# Power_Supply.net
KiCad netlist of a schematic drawn in Altium Designer
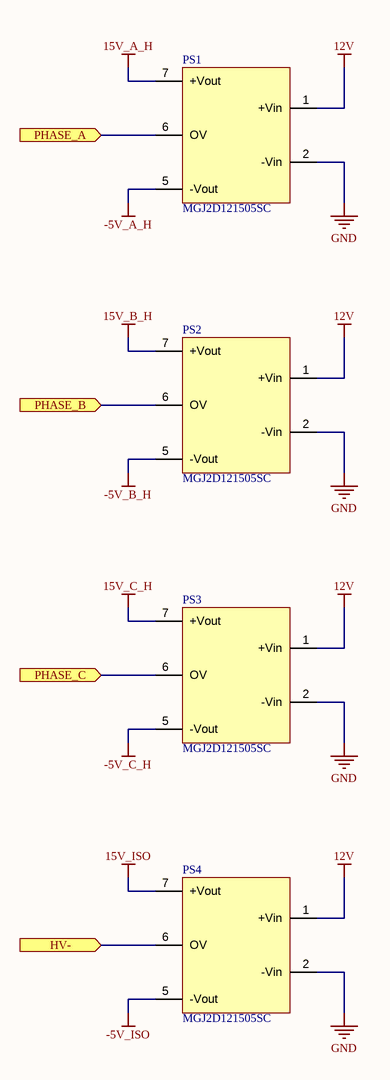
[diagram p0: Power Supply.SchDoc]

(export (version "E")
  (design (tool "Eeschema 10.0.6"))
  (components
    (comp (ref "PS1")
      (value "MGJ2D121505SC")
      (description "DC DC CONVERTER 15V -5V 2W")
      (libsource (lib "3PO") (part "MGJ2D121505SC"))
    )
    (comp (ref "PS2")
      (value "MGJ2D121505SC")
      (description "DC DC CONVERTER 15V -5V 2W")
      (libsource (lib "3PO") (part "MGJ2D121505SC"))
    )
    (comp (ref "PS3")
      (value "MGJ2D121505SC")
      (description "DC DC CONVERTER 15V -5V 2W")
      (libsource (lib "3PO") (part "MGJ2D121505SC"))
    )
    (comp (ref "PS4")
      (value "MGJ2D121505SC")
      (description "DC DC CONVERTER 15V -5V 2W")
      (libsource (lib "3PO") (part "MGJ2D121505SC"))
    )
  )
  (nets
    (net (code "1") (name "-5V_A_H") (class "Default")
      (node (ref "PS1") (pin "5") (pinfunction "-Vout_5") (pintype "passive"))
    )
    (net (code "2") (name "-5V_B_H") (class "Default")
      (node (ref "PS2") (pin "5") (pinfunction "-Vout_5") (pintype "passive"))
    )
    (net (code "3") (name "-5V_C_H") (class "Default")
      (node (ref "PS3") (pin "5") (pinfunction "-Vout_5") (pintype "passive"))
    )
    (net (code "4") (name "-5V_ISO") (class "Default")
      (node (ref "PS4") (pin "5") (pinfunction "-Vout_5") (pintype "passive"))
    )
    (net (code "5") (name "/HV-") (class "Default")
      (node (ref "PS4") (pin "6") (pinfunction "OV_6") (pintype "passive"))
    )
    (net (code "6") (name "/PHASE_A") (class "Default")
      (node (ref "PS1") (pin "6") (pinfunction "OV_6") (pintype "passive"))
    )
    (net (code "7") (name "/PHASE_B") (class "Default")
      (node (ref "PS2") (pin "6") (pinfunction "OV_6") (pintype "passive"))
    )
    (net (code "8") (name "/PHASE_C") (class "Default")
      (node (ref "PS3") (pin "6") (pinfunction "OV_6") (pintype "passive"))
    )
    (net (code "9") (name "12V") (class "Default")
      (node (ref "PS1") (pin "1") (pinfunction "+Vin_1") (pintype "passive"))
      (node (ref "PS2") (pin "1") (pinfunction "+Vin_1") (pintype "passive"))
      (node (ref "PS3") (pin "1") (pinfunction "+Vin_1") (pintype "passive"))
      (node (ref "PS4") (pin "1") (pinfunction "+Vin_1") (pintype "passive"))
    )
    (net (code "10") (name "15V_A_H") (class "Default")
      (node (ref "PS1") (pin "7") (pinfunction "+Vout_7") (pintype "passive"))
    )
    (net (code "11") (name "15V_B_H") (class "Default")
      (node (ref "PS2") (pin "7") (pinfunction "+Vout_7") (pintype "passive"))
    )
    (net (code "12") (name "15V_C_H") (class "Default")
      (node (ref "PS3") (pin "7") (pinfunction "+Vout_7") (pintype "passive"))
    )
    (net (code "13") (name "15V_ISO") (class "Default")
      (node (ref "PS4") (pin "7") (pinfunction "+Vout_7") (pintype "passive"))
    )
    (net (code "14") (name "GND") (class "Default")
      (node (ref "PS1") (pin "2") (pinfunction "-Vin_2") (pintype "passive"))
      (node (ref "PS2") (pin "2") (pinfunction "-Vin_2") (pintype "passive"))
      (node (ref "PS3") (pin "2") (pinfunction "-Vin_2") (pintype "passive"))
      (node (ref "PS4") (pin "2") (pinfunction "-Vin_2") (pintype "passive"))
    )
  )
)
